# rotenc.net
KiCad netlist of a schematic drawn in EAGLE
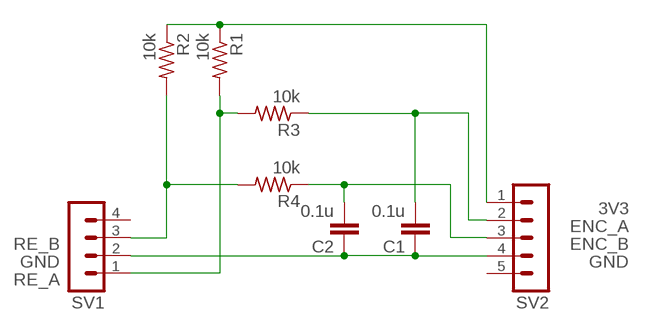
[diagram p0: schematic, sheet 1]

(export (version "E")
  (design (tool "Eeschema 10.0.6"))
  (components
    (comp (ref "C1")
      (value "0.1u")
      (footprint "eagle-import:C025-025X050")
      (libsource (lib "eagle-import") (part "C-EU025-025X050"))
    )
    (comp (ref "C2")
      (value "0.1u")
      (footprint "eagle-import:C025-025X050")
      (libsource (lib "eagle-import") (part "C-EU025-025X050"))
    )
    (comp (ref "R1")
      (value "10k")
      (footprint "eagle-import:0204_7")
      (libsource (lib "eagle-import") (part "R-US_0204/7"))
    )
    (comp (ref "R2")
      (value "10k")
      (footprint "eagle-import:0204_7")
      (libsource (lib "eagle-import") (part "R-US_0204/7"))
    )
    (comp (ref "R3")
      (value "10k")
      (footprint "eagle-import:0204_7")
      (libsource (lib "eagle-import") (part "R-US_0204/7"))
    )
    (comp (ref "R4")
      (value "10k")
      (footprint "eagle-import:0204_7")
      (libsource (lib "eagle-import") (part "R-US_0204/7"))
    )
    (comp (ref "SV1")
      (value "MA04-1")
      (footprint "eagle-import:MA04-1")
      (libsource (lib "eagle-import") (part "MA04-1"))
    )
    (comp (ref "SV2")
      (value "MA05-1")
      (footprint "eagle-import:MA05-1")
      (libsource (lib "eagle-import") (part "MA05-1"))
    )
  )
  (nets
    (net (code "1") (name "/3V3") (class "Default")
      (node (ref "R1") (pin "1") (pinfunction "1_1") (pintype "passive"))
      (node (ref "R2") (pin "1") (pinfunction "1_1") (pintype "passive"))
      (node (ref "SV2") (pin "1") (pinfunction "1_1") (pintype "passive"))
    )
    (net (code "2") (name "/ENC_A") (class "Default")
      (node (ref "C1") (pin "2") (pinfunction "2_2") (pintype "passive"))
      (node (ref "R3") (pin "1") (pinfunction "1_1") (pintype "passive"))
      (node (ref "SV2") (pin "2") (pinfunction "2_2") (pintype "passive"))
    )
    (net (code "3") (name "/ENC_B") (class "Default")
      (node (ref "C2") (pin "2") (pinfunction "2_2") (pintype "passive"))
      (node (ref "R4") (pin "1") (pinfunction "1_1") (pintype "passive"))
      (node (ref "SV2") (pin "3") (pinfunction "3_3") (pintype "passive"))
    )
    (net (code "4") (name "/GND") (class "Default")
      (node (ref "C1") (pin "1") (pinfunction "1_1") (pintype "passive"))
      (node (ref "C2") (pin "1") (pinfunction "1_1") (pintype "passive"))
      (node (ref "SV1") (pin "2") (pinfunction "2_2") (pintype "passive"))
      (node (ref "SV2") (pin "4") (pinfunction "4_4") (pintype "passive"))
    )
    (net (code "5") (name "/RE_A") (class "Default")
      (node (ref "R1") (pin "2") (pinfunction "2_2") (pintype "passive"))
      (node (ref "R3") (pin "2") (pinfunction "2_2") (pintype "passive"))
      (node (ref "SV1") (pin "1") (pinfunction "1_1") (pintype "passive"))
    )
    (net (code "6") (name "/RE_B") (class "Default")
      (node (ref "R2") (pin "2") (pinfunction "2_2") (pintype "passive"))
      (node (ref "R4") (pin "2") (pinfunction "2_2") (pintype "passive"))
      (node (ref "SV1") (pin "3") (pinfunction "3_3") (pintype "passive"))
    )
    (net (code "7") (name "unconnected-(SV1-Pad4)") (class "Default")
      (node (ref "SV1") (pin "4") (pinfunction "4_4") (pintype "passive"))
    )
    (net (code "8") (name "unconnected-(SV2-Pad5)") (class "Default")
      (node (ref "SV2") (pin "5") (pinfunction "5_5") (pintype "passive"))
    )
  )
)
